# MidiMon_B.net
KiCad netlist of a schematic drawn in EAGLE
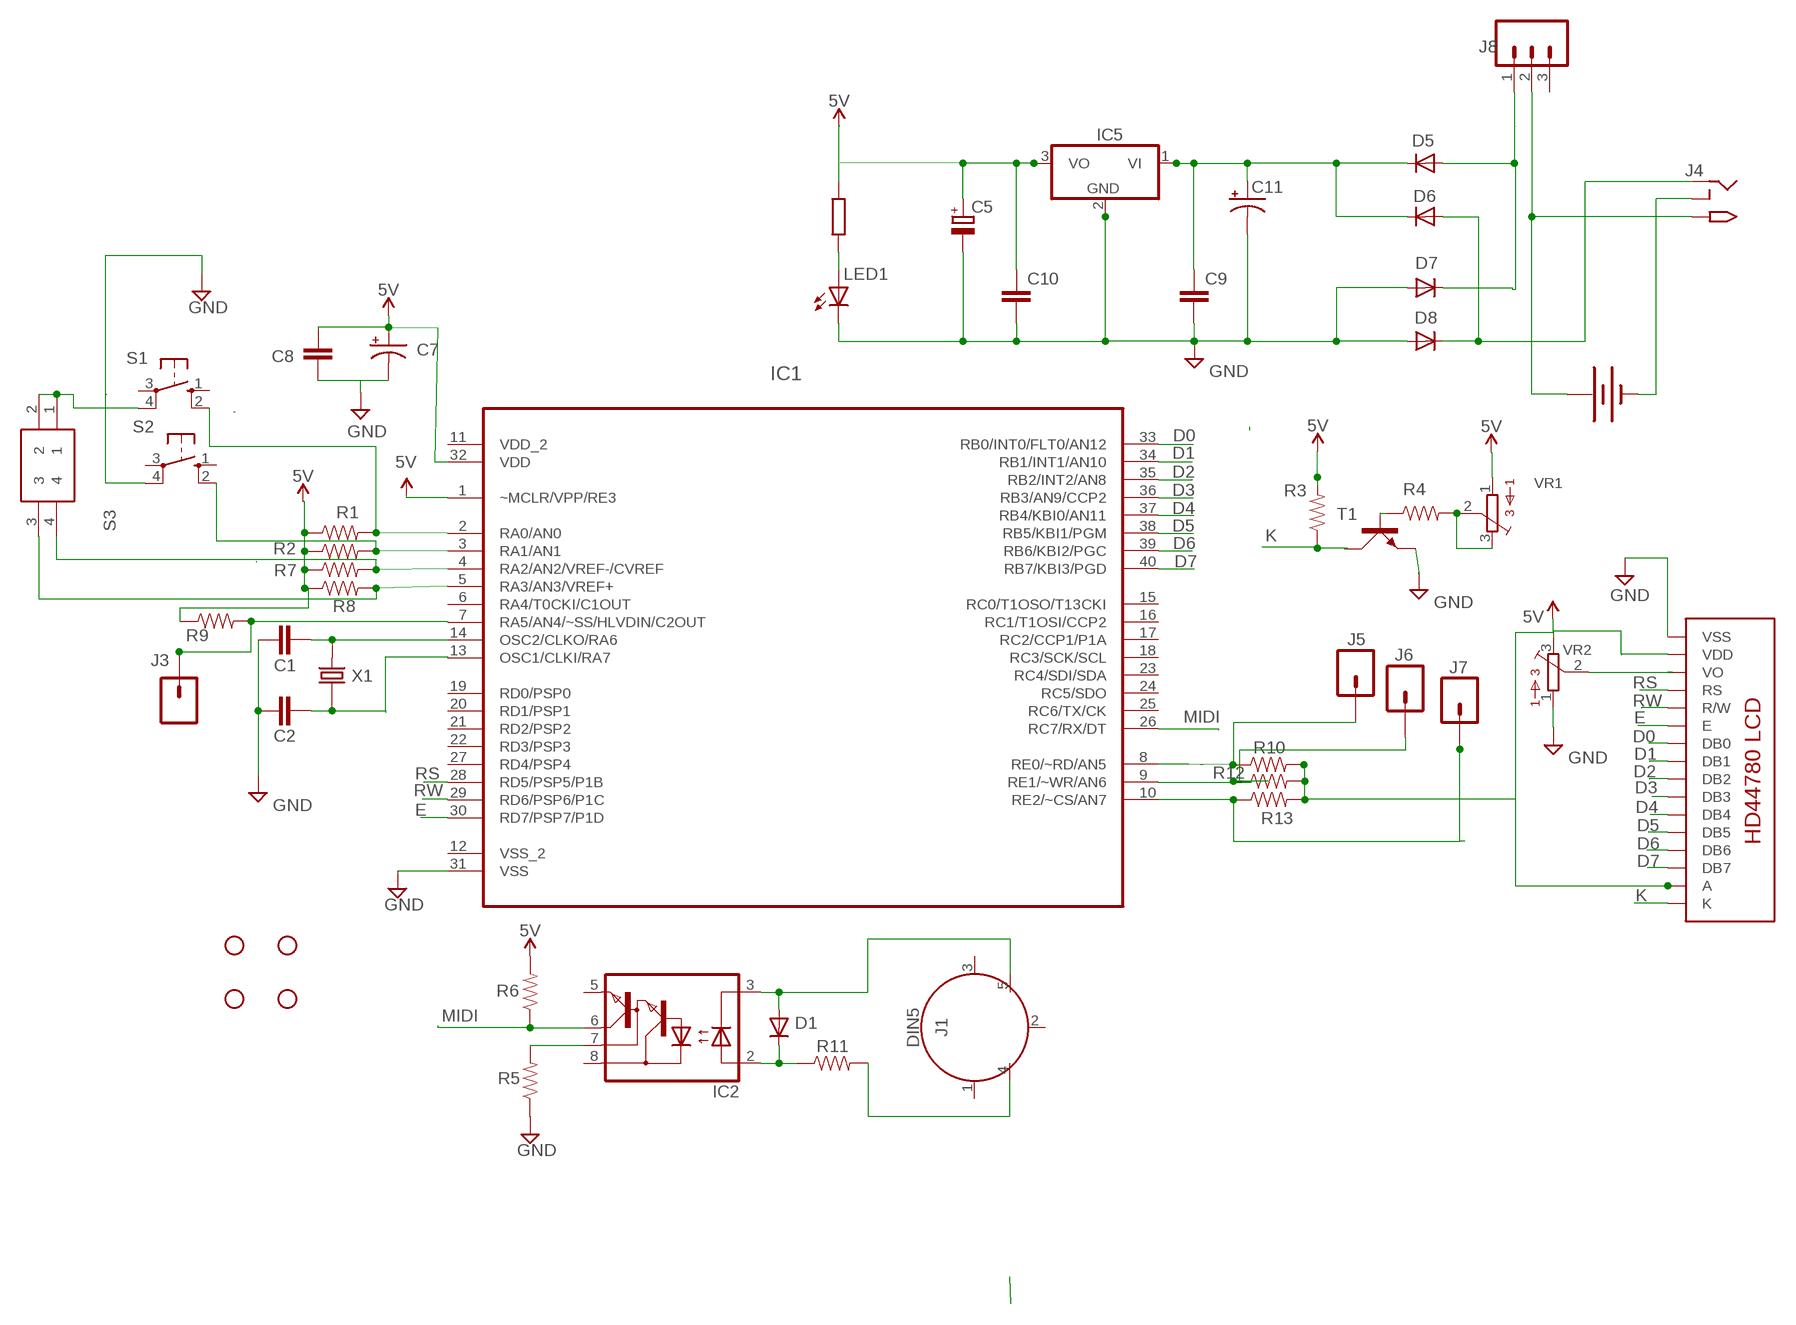
[diagram p0: schematic, sheet 1]

(export (version "E")
  (design (tool "Eeschema 10.0.6"))
  (components
    (comp (ref "BAT1")
      (value "BATTERY")
      (footprint "eagle-import:PP3_BATTERBOX")
      (libsource (lib "eagle-import") (part "BATTERY"))
    )
    (comp (ref "C1")
      (value "18pF")
      (footprint "eagle-import:CAP-PTH-2.54")
      (libsource (lib "eagle-import") (part "22PF-PTH-2.54MM-200V-5%"))
    )
    (comp (ref "C2")
      (value "18pF")
      (footprint "eagle-import:CAP-PTH-2.54")
      (libsource (lib "eagle-import") (part "22PF-PTH-2.54MM-200V-5%"))
    )
    (comp (ref "C5")
      (value "10uf")
      (footprint "eagle-import:E2,5-7")
      (libsource (lib "eagle-import") (part "CPOL-EUE2.5-7"))
    )
    (comp (ref "C7")
      (value "10uF")
      (footprint "eagle-import:CPOL-RADIAL-2.5MM-5MM")
      (libsource (lib "eagle-import") (part "10UF-POLAR-RADIAL-2.5MM-25V-20%"))
    )
    (comp (ref "C8")
      (value "0.1uF")
      (footprint "eagle-import:CAP-PTH-SMALL-KIT")
      (libsource (lib "eagle-import") (part "0.1UF-KIT-EZ-50V-20%"))
    )
    (comp (ref "C9")
      (value "330nf")
      (footprint "eagle-import:C025-024X044")
      (libsource (lib "eagle-import") (part "C-EU025-024X044"))
    )
    (comp (ref "C10")
      (value "100nf")
      (footprint "eagle-import:C025-024X044")
      (libsource (lib "eagle-import") (part "C-EU025-024X044"))
    )
    (comp (ref "C11")
      (value "2200uf")
      (footprint "eagle-import:E5-10,5")
      (libsource (lib "eagle-import") (part "CPOL-USE5-10.5"))
    )
    (comp (ref "D1")
      (value "DIODEDO-1N4148")
      (footprint "eagle-import:DO-1N4148")
      (libsource (lib "eagle-import") (part "DIODEDO-1N4148"))
    )
    (comp (ref "D5")
      (value "1N4004")
      (footprint "eagle-import:DO-VERT")
      (libsource (lib "eagle-import") (part "1N4004"))
    )
    (comp (ref "D6")
      (value "1N4004")
      (footprint "eagle-import:DO-VERT")
      (libsource (lib "eagle-import") (part "1N4004"))
    )
    (comp (ref "D7")
      (value "1N4004")
      (footprint "eagle-import:DO-VERT")
      (libsource (lib "eagle-import") (part "1N4004"))
    )
    (comp (ref "D8")
      (value "1N4004")
      (footprint "eagle-import:DO-VERT")
      (libsource (lib "eagle-import") (part "1N4004"))
    )
    (comp (ref "H1")
      (value "STAND-OFFTIGHT")
      (footprint "eagle-import:STAND-OFF-TIGHT")
      (libsource (lib "eagle-import") (part "STAND-OFFTIGHT"))
    )
    (comp (ref "H2")
      (value "STAND-OFFTIGHT")
      (footprint "eagle-import:STAND-OFF-TIGHT")
      (libsource (lib "eagle-import") (part "STAND-OFFTIGHT"))
    )
    (comp (ref "H3")
      (value "STAND-OFFTIGHT")
      (footprint "eagle-import:STAND-OFF-TIGHT")
      (libsource (lib "eagle-import") (part "STAND-OFFTIGHT"))
    )
    (comp (ref "H4")
      (value "STAND-OFFTIGHT")
      (footprint "eagle-import:STAND-OFF-TIGHT")
      (libsource (lib "eagle-import") (part "STAND-OFFTIGHT"))
    )
    (comp (ref "IC1")
      (value "PIC18F4520-I/P")
      (footprint "eagle-import:DIP254P1524X533-40")
      (fields (field (name "MF") "Microchip"))
      (libsource (lib "eagle-import") (part "PIC18F4520-I/P"))
    )
    (comp (ref "IC2")
      (value "6N138")
      (footprint "eagle-import:DIL08")
      (fields (field (name "MF") "VISHAY/TELEFUNKEN"))
      (libsource (lib "eagle-import") (part "6N138"))
    )
    (comp (ref "IC5")
      (value "7805TV")
      (footprint "eagle-import:TO220V")
      (libsource (lib "eagle-import") (part "78TV05"))
    )
    (comp (ref "J1")
      (value "DIN5")
      (footprint "eagle-import:DIN5-RA-PTH")
      (libsource (lib "eagle-import") (part "DIN5"))
    )
    (comp (ref "J3")
      (value "CONN_01")
      (footprint "eagle-import:1X01")
      (libsource (lib "eagle-import") (part "CONN_01"))
    )
    (comp (ref "J4")
      (value "2.1MMJACKTHM")
      (footprint "eagle-import:PJ-102A")
      (libsource (lib "eagle-import") (part "2.1MMJACKTHM"))
    )
    (comp (ref "J5")
      (value "CONN_01")
      (footprint "eagle-import:1X01")
      (libsource (lib "eagle-import") (part "CONN_01"))
    )
    (comp (ref "J6")
      (value "CONN_01")
      (footprint "eagle-import:1X01")
      (libsource (lib "eagle-import") (part "CONN_01"))
    )
    (comp (ref "J7")
      (value "CONN_01")
      (footprint "eagle-import:1X01")
      (libsource (lib "eagle-import") (part "CONN_01"))
    )
    (comp (ref "J8")
      (value "CONN_03")
      (footprint "eagle-import:1X03")
      (libsource (lib "eagle-import") (part "CONN_03"))
    )
    (comp (ref "LED1")
      (value "LED3MM")
      (footprint "eagle-import:LED3MM")
      (libsource (lib "eagle-import") (part "LED3MM"))
    )
    (comp (ref "R1")
      (value "10k")
      (footprint "eagle-import:AXIAL-0.3")
      (libsource (lib "eagle-import") (part "1KOHM-HORIZ-1/4W-5%"))
    )
    (comp (ref "R2")
      (value "10k")
      (footprint "eagle-import:AXIAL-0.3")
      (libsource (lib "eagle-import") (part "1KOHM-HORIZ-1/4W-5%"))
    )
    (comp (ref "R3")
      (value "10k")
      (footprint "eagle-import:AXIAL-0.3")
      (libsource (lib "eagle-import") (part "1KOHM-HORIZ-1/4W-5%"))
    )
    (comp (ref "R4")
      (value "10k")
      (footprint "eagle-import:AXIAL-0.3")
      (libsource (lib "eagle-import") (part "1KOHM-HORIZ-1/4W-5%"))
    )
    (comp (ref "R5")
      (value "5.6k")
      (footprint "eagle-import:AXIAL-0.3")
      (libsource (lib "eagle-import") (part "1KOHM-HORIZ-1/4W-5%"))
    )
    (comp (ref "R6")
      (value "1.2k")
      (footprint "eagle-import:AXIAL-0.3")
      (libsource (lib "eagle-import") (part "1KOHM-HORIZ-1/4W-5%"))
    )
    (comp (ref "R7")
      (value "10k")
      (footprint "eagle-import:AXIAL-0.3")
      (libsource (lib "eagle-import") (part "1KOHM-HORIZ-1/4W-5%"))
    )
    (comp (ref "R8")
      (value "10k")
      (footprint "eagle-import:AXIAL-0.3")
      (libsource (lib "eagle-import") (part "1KOHM-HORIZ-1/4W-5%"))
    )
    (comp (ref "R9")
      (value "10k")
      (footprint "eagle-import:AXIAL-0.3")
      (libsource (lib "eagle-import") (part "1KOHM-HORIZ-1/4W-5%"))
    )
    (comp (ref "R10")
      (value "10k")
      (footprint "eagle-import:AXIAL-0.3")
      (libsource (lib "eagle-import") (part "1KOHM-HORIZ-1/4W-5%"))
    )
    (comp (ref "R11")
      (value "220")
      (footprint "eagle-import:AXIAL-0.3")
      (libsource (lib "eagle-import") (part "1KOHM-HORIZ-1/4W-5%"))
    )
    (comp (ref "R12")
      (value "10k")
      (footprint "eagle-import:AXIAL-0.3")
      (libsource (lib "eagle-import") (part "1KOHM-HORIZ-1/4W-5%"))
    )
    (comp (ref "R13")
      (value "10k")
      (footprint "eagle-import:AXIAL-0.3")
      (libsource (lib "eagle-import") (part "1KOHM-HORIZ-1/4W-5%"))
    )
    (comp (ref "R20")
      (value "1k")
      (footprint "eagle-import:0207_7")
      (libsource (lib "eagle-import") (part "R-EU_0207/7"))
    )
    (comp (ref "S1")
      (value "40-XX")
      (footprint "eagle-import:B3F-40XX")
      (fields (field (name "MF") "OMRON COMPONENTS USA") (field (name "MPN") "B3F-4000"))
      (libsource (lib "eagle-import") (part "40-XX"))
    )
    (comp (ref "S2")
      (value "40-XX")
      (footprint "eagle-import:B3F-40XX")
      (fields (field (name "MF") "OMRON COMPONENTS USA") (field (name "MPN") "B3F-4000"))
      (libsource (lib "eagle-import") (part "40-XX"))
    )
    (comp (ref "S3")
      (value "195-2MST")
      (footprint "eagle-import:DIPS774W56P254L726H790Q4N")
      (fields (field (name "MOUSER_PART_NUMBER") "774-1952MST"))
      (libsource (lib "eagle-import") (part "195-2MST"))
    )
    (comp (ref "T1")
      (value "2N3904")
      (footprint "eagle-import:TO92D")
      (libsource (lib "eagle-import") (part "2N3904"))
    )
    (comp (ref "U$2")
      (value "LCD-HD4478020X4-3HOLES")
      (footprint "eagle-import:LCD-20X4-3HOLES")
      (libsource (lib "eagle-import") (part "LCD-HD4478020X4-3HOLES"))
    )
    (comp (ref "VR1")
      (value "BOURNS_3362P_TRIMMERP")
      (footprint "eagle-import:BOURNS_3362P_TRIMMER")
      (libsource (lib "eagle-import") (part "BOURNS_3362P_TRIMMERP"))
    )
    (comp (ref "VR2")
      (value "BOURNS_3362P_TRIMMERP")
      (footprint "eagle-import:BOURNS_3362P_TRIMMER")
      (libsource (lib "eagle-import") (part "BOURNS_3362P_TRIMMERP"))
    )
    (comp (ref "X1")
      (value "ECS-100-18-4X")
      (footprint "eagle-import:XTAL_ECS-100-18-4X")
      (fields (field (name "DIGI-KEY_PART_NUMBER") "X1080-ND") (field (name "MF") "ECS Inc."))
      (libsource (lib "eagle-import") (part "ECS-100-18-4X"))
    )
  )
  (nets
    (net (code "1") (name "/D0") (class "Default")
      (node (ref "IC1") (pin "33") (pinfunction "RB0/INT0/FLT0/AN12_33") (pintype "bidirectional"))
      (node (ref "U$2") (pin "P$7") (pinfunction "DB0_P$7") (pintype "bidirectional"))
    )
    (net (code "2") (name "/D1") (class "Default")
      (node (ref "IC1") (pin "34") (pinfunction "RB1/INT1/AN10_34") (pintype "bidirectional"))
      (node (ref "U$2") (pin "P$8") (pinfunction "DB1_P$8") (pintype "bidirectional"))
    )
    (net (code "3") (name "/D2") (class "Default")
      (node (ref "IC1") (pin "35") (pinfunction "RB2/INT2/AN8_35") (pintype "bidirectional"))
      (node (ref "U$2") (pin "P$9") (pinfunction "DB2_P$9") (pintype "bidirectional"))
    )
    (net (code "4") (name "/D3") (class "Default")
      (node (ref "IC1") (pin "36") (pinfunction "RB3/AN9/CCP2_36") (pintype "bidirectional"))
      (node (ref "U$2") (pin "P$10") (pinfunction "DB3_P$10") (pintype "bidirectional"))
    )
    (net (code "5") (name "/D4") (class "Default")
      (node (ref "IC1") (pin "37") (pinfunction "RB4/KBI0/AN11_37") (pintype "bidirectional"))
      (node (ref "U$2") (pin "P$11") (pinfunction "DB4_P$11") (pintype "bidirectional"))
    )
    (net (code "6") (name "/D5") (class "Default")
      (node (ref "IC1") (pin "38") (pinfunction "RB5/KBI1/PGM_38") (pintype "bidirectional"))
      (node (ref "U$2") (pin "P$12") (pinfunction "DB5_P$12") (pintype "bidirectional"))
    )
    (net (code "7") (name "/D6") (class "Default")
      (node (ref "IC1") (pin "39") (pinfunction "RB6/KBI2/PGC_39") (pintype "bidirectional"))
      (node (ref "U$2") (pin "P$13") (pinfunction "DB6_P$13") (pintype "bidirectional"))
    )
    (net (code "8") (name "/D7") (class "Default")
      (node (ref "IC1") (pin "40") (pinfunction "RB7/KBI3/PGD_40") (pintype "bidirectional"))
      (node (ref "U$2") (pin "P$14") (pinfunction "DB7_P$14") (pintype "bidirectional"))
    )
    (net (code "9") (name "/E") (class "Default")
      (node (ref "IC1") (pin "30") (pinfunction "RD7/PSP7/P1D_30") (pintype "bidirectional"))
      (node (ref "U$2") (pin "P$6") (pinfunction "E_P$6") (pintype "input"))
    )
    (net (code "10") (name "/K") (class "Default")
      (node (ref "R3") (pin "P$1") (pinfunction "1_P$1") (pintype "passive"))
      (node (ref "T1") (pin "C") (pinfunction "C_C") (pintype "passive"))
      (node (ref "U$2") (pin "P$16") (pinfunction "K_P$16") (pintype "power_in"))
    )
    (net (code "11") (name "/MIDI") (class "Default")
      (node (ref "IC1") (pin "26") (pinfunction "RC7/RX/DT_26") (pintype "bidirectional"))
      (node (ref "IC2") (pin "6") (pinfunction "VO_6") (pintype "passive"))
      (node (ref "R6") (pin "P$1") (pinfunction "1_P$1") (pintype "passive"))
    )
    (net (code "12") (name "/RS") (class "Default")
      (node (ref "IC1") (pin "28") (pinfunction "RD5/PSP5/P1B_28") (pintype "bidirectional"))
      (node (ref "U$2") (pin "P$4") (pinfunction "RS_P$4") (pintype "input"))
    )
    (net (code "13") (name "/RW") (class "Default")
      (node (ref "IC1") (pin "29") (pinfunction "RD6/PSP6/P1C_29") (pintype "bidirectional"))
      (node (ref "U$2") (pin "P$5") (pinfunction "R/W_P$5") (pintype "input"))
    )
    (net (code "14") (name "/VDD_2") (class "Default")
      (node (ref "IC1") (pin "11") (pinfunction "VDD_2_11") (pintype "power_in"))
    )
    (net (code "15") (name "/VSS_2") (class "Default")
      (node (ref "IC1") (pin "12") (pinfunction "VSS_2_12") (pintype "power_in"))
    )
    (net (code "16") (name "5V") (class "Default")
      (node (ref "C7") (pin "1") (pinfunction "+_1") (pintype "passive"))
      (node (ref "C8") (pin "2") (pinfunction "2_2") (pintype "passive"))
      (node (ref "IC1") (pin "1") (pinfunction "~{MCLR/VPP/RE3}_1") (pintype "input"))
      (node (ref "IC1") (pin "32") (pinfunction "VDD_32") (pintype "power_in"))
      (node (ref "R1") (pin "P$1") (pinfunction "1_P$1") (pintype "passive"))
      (node (ref "R10") (pin "P$2") (pinfunction "2_P$2") (pintype "passive"))
      (node (ref "R12") (pin "P$2") (pinfunction "2_P$2") (pintype "passive"))
      (node (ref "R13") (pin "P$2") (pinfunction "2_P$2") (pintype "passive"))
      (node (ref "R2") (pin "P$1") (pinfunction "1_P$1") (pintype "passive"))
      (node (ref "R3") (pin "P$2") (pinfunction "2_P$2") (pintype "passive"))
      (node (ref "R6") (pin "P$2") (pinfunction "2_P$2") (pintype "passive"))
      (node (ref "R7") (pin "P$1") (pinfunction "1_P$1") (pintype "passive"))
      (node (ref "R8") (pin "P$1") (pinfunction "1_P$1") (pintype "passive"))
      (node (ref "R9") (pin "P$1") (pinfunction "1_P$1") (pintype "passive"))
      (node (ref "U$2") (pin "P$15") (pinfunction "A_P$15") (pintype "power_in"))
      (node (ref "VR1") (pin "1") (pinfunction "1_1") (pintype "passive"))
    )
    (net (code "17") (name "GND") (class "Default")
      (node (ref "C1") (pin "1") (pinfunction "1_1") (pintype "passive"))
      (node (ref "C10") (pin "2") (pinfunction "2_2") (pintype "passive"))
      (node (ref "C11") (pin "-") (pinfunction "-_-") (pintype "passive"))
      (node (ref "C2") (pin "1") (pinfunction "1_1") (pintype "passive"))
      (node (ref "C5") (pin "-") (pinfunction "-_-") (pintype "passive"))
      (node (ref "C7") (pin "2") (pinfunction "-_2") (pintype "passive"))
      (node (ref "C8") (pin "1") (pinfunction "1_1") (pintype "passive"))
      (node (ref "C9") (pin "2") (pinfunction "2_2") (pintype "passive"))
      (node (ref "D7") (pin "A") (pinfunction "A_A") (pintype "passive"))
      (node (ref "D8") (pin "A") (pinfunction "A_A") (pintype "passive"))
      (node (ref "IC1") (pin "31") (pinfunction "VSS_31") (pintype "power_in"))
      (node (ref "IC5") (pin "2") (pinfunction "GND_2") (pintype "passive"))
      (node (ref "LED1") (pin "K") (pinfunction "C_K") (pintype "passive"))
      (node (ref "R5") (pin "P$1") (pinfunction "1_P$1") (pintype "passive"))
      (node (ref "S1") (pin "4") (pinfunction "P1_4") (pintype "passive"))
      (node (ref "S2") (pin "4") (pinfunction "P1_4") (pintype "passive"))
      (node (ref "S3") (pin "1") (pinfunction "1_1") (pintype "bidirectional"))
      (node (ref "S3") (pin "2") (pinfunction "2_2") (pintype "bidirectional"))
      (node (ref "T1") (pin "E") (pinfunction "E_E") (pintype "passive"))
      (node (ref "U$2") (pin "P$1") (pinfunction "VSS_P$1") (pintype "power_in"))
      (node (ref "VR2") (pin "1") (pinfunction "1_1") (pintype "passive"))
    )
    (net (code "18") (name "Net-(BAT1-+)") (class "Default")
      (node (ref "BAT1") (pin "9V") (pinfunction "+_9V") (pintype "power_in"))
      (node (ref "J4") (pin "TIP") (pinfunction "TIP_TIP") (pintype "bidirectional"))
      (node (ref "J8") (pin "2") (pinfunction "2_2") (pintype "passive"))
    )
    (net (code "19") (name "Net-(BAT1--)") (class "Default")
      (node (ref "BAT1") (pin "0V") (pinfunction "-_0V") (pintype "power_in"))
      (node (ref "J4") (pin "RING_SW") (pinfunction "RING_SW_RING_SW") (pintype "bidirectional"))
    )
    (net (code "20") (name "Net-(D5-PadA)") (class "Default")
      (node (ref "D5") (pin "A") (pinfunction "A_A") (pintype "passive"))
      (node (ref "D7") (pin "C") (pinfunction "C_C") (pintype "passive"))
      (node (ref "J8") (pin "1") (pinfunction "1_1") (pintype "passive"))
    )
    (net (code "21") (name "Net-(D6-PadA)") (class "Default")
      (node (ref "D6") (pin "A") (pinfunction "A_A") (pintype "passive"))
      (node (ref "D8") (pin "C") (pinfunction "C_C") (pintype "passive"))
      (node (ref "J4") (pin "RING") (pinfunction "RING_RING") (pintype "bidirectional"))
    )
    (net (code "22") (name "Net-(IC1-OSC1{slash}CLKI{slash}RA7)") (class "Default")
      (node (ref "C2") (pin "2") (pinfunction "2_2") (pintype "passive"))
      (node (ref "IC1") (pin "13") (pinfunction "OSC1/CLKI/RA7_13") (pintype "bidirectional"))
      (node (ref "X1") (pin "1") (pinfunction "1_1") (pintype "passive"))
    )
    (net (code "23") (name "Net-(IC1-OSC2{slash}CLKO{slash}RA6)") (class "Default")
      (node (ref "C1") (pin "2") (pinfunction "2_2") (pintype "passive"))
      (node (ref "IC1") (pin "14") (pinfunction "OSC2/CLKO/RA6_14") (pintype "bidirectional"))
      (node (ref "X1") (pin "2") (pinfunction "2_2") (pintype "passive"))
    )
    (net (code "24") (name "Net-(IC1-RA0{slash}AN0)") (class "Default")
      (node (ref "IC1") (pin "2") (pinfunction "RA0/AN0_2") (pintype "bidirectional"))
      (node (ref "R1") (pin "P$2") (pinfunction "2_P$2") (pintype "passive"))
      (node (ref "S1") (pin "2") (pinfunction "S1_2") (pintype "passive"))
    )
    (net (code "25") (name "Net-(IC1-RA1{slash}AN1)") (class "Default")
      (node (ref "IC1") (pin "3") (pinfunction "RA1/AN1_3") (pintype "bidirectional"))
      (node (ref "R2") (pin "P$2") (pinfunction "2_P$2") (pintype "passive"))
      (node (ref "S2") (pin "2") (pinfunction "S1_2") (pintype "passive"))
    )
    (net (code "26") (name "Net-(IC1-RA2{slash}AN2{slash}VREF-{slash}CVREF)") (class "Default")
      (node (ref "IC1") (pin "4") (pinfunction "RA2/AN2/VREF-/CVREF_4") (pintype "bidirectional"))
      (node (ref "R7") (pin "P$2") (pinfunction "2_P$2") (pintype "passive"))
      (node (ref "S3") (pin "4") (pinfunction "4_4") (pintype "bidirectional"))
    )
    (net (code "27") (name "Net-(IC1-RA3{slash}AN3{slash}VREF+)") (class "Default")
      (node (ref "IC1") (pin "5") (pinfunction "RA3/AN3/VREF+_5") (pintype "bidirectional"))
      (node (ref "R8") (pin "P$2") (pinfunction "2_P$2") (pintype "passive"))
      (node (ref "S3") (pin "3") (pinfunction "3_3") (pintype "bidirectional"))
    )
    (net (code "28") (name "Net-(IC1-RA5{slash}AN4{slash}~{SS{slash}HLVDIN{slash}C2OUT})") (class "Default")
      (node (ref "IC1") (pin "7") (pinfunction "RA5/AN4/~{SS/HLVDIN/C2OUT}_7") (pintype "bidirectional"))
      (node (ref "J3") (pin "1") (pinfunction "1_1") (pintype "passive"))
      (node (ref "R9") (pin "P$2") (pinfunction "2_P$2") (pintype "passive"))
    )
    (net (code "29") (name "Net-(IC1-RE0{slash}~{RD{slash}AN5})") (class "Default")
      (node (ref "IC1") (pin "8") (pinfunction "RE0/~{RD/AN5}_8") (pintype "bidirectional"))
      (node (ref "J5") (pin "1") (pinfunction "1_1") (pintype "passive"))
      (node (ref "R10") (pin "P$1") (pinfunction "1_P$1") (pintype "passive"))
    )
    (net (code "30") (name "Net-(IC1-RE1{slash}~{WR{slash}AN6})") (class "Default")
      (node (ref "IC1") (pin "9") (pinfunction "RE1/~{WR/AN6}_9") (pintype "bidirectional"))
      (node (ref "J6") (pin "1") (pinfunction "1_1") (pintype "passive"))
      (node (ref "R12") (pin "P$1") (pinfunction "1_P$1") (pintype "passive"))
    )
    (net (code "31") (name "Net-(IC1-RE2{slash}~{CS{slash}AN7})") (class "Default")
      (node (ref "IC1") (pin "10") (pinfunction "RE2/~{CS/AN7}_10") (pintype "bidirectional"))
      (node (ref "J7") (pin "1") (pinfunction "1_1") (pintype "passive"))
      (node (ref "R13") (pin "P$1") (pinfunction "1_P$1") (pintype "passive"))
    )
    (net (code "32") (name "Net-(IC2-A)") (class "Default")
      (node (ref "D1") (pin "C") (pinfunction "C_C") (pintype "passive"))
      (node (ref "IC2") (pin "2") (pinfunction "A_2") (pintype "passive"))
      (node (ref "R11") (pin "P$1") (pinfunction "1_P$1") (pintype "passive"))
    )
    (net (code "33") (name "Net-(IC2-C)") (class "Default")
      (node (ref "D1") (pin "A") (pinfunction "A_A") (pintype "passive"))
      (node (ref "IC2") (pin "3") (pinfunction "C_3") (pintype "passive"))
      (node (ref "J1") (pin "5") (pinfunction "5_5") (pintype "bidirectional"))
    )
    (net (code "34") (name "Net-(IC2-VB)") (class "Default")
      (node (ref "IC2") (pin "7") (pinfunction "VB_7") (pintype "passive"))
      (node (ref "R5") (pin "P$2") (pinfunction "2_P$2") (pintype "passive"))
    )
    (net (code "35") (name "Net-(IC5-VI)") (class "Default")
      (node (ref "C11") (pin "+") (pinfunction "+_+") (pintype "passive"))
      (node (ref "C9") (pin "1") (pinfunction "1_1") (pintype "passive"))
      (node (ref "D5") (pin "C") (pinfunction "C_C") (pintype "passive"))
      (node (ref "D6") (pin "C") (pinfunction "C_C") (pintype "passive"))
      (node (ref "IC5") (pin "1") (pinfunction "VI_1") (pintype "input"))
    )
    (net (code "36") (name "Net-(IC5-VO)") (class "Default")
      (node (ref "C10") (pin "1") (pinfunction "1_1") (pintype "passive"))
      (node (ref "C5") (pin "+") (pinfunction "+_+") (pintype "passive"))
      (node (ref "IC5") (pin "3") (pinfunction "VO_3") (pintype "passive"))
      (node (ref "R20") (pin "1") (pinfunction "1_1") (pintype "passive"))
    )
    (net (code "37") (name "Net-(LED1-PadA)") (class "Default")
      (node (ref "LED1") (pin "A") (pinfunction "A_A") (pintype "passive"))
      (node (ref "R20") (pin "2") (pinfunction "2_2") (pintype "passive"))
    )
    (net (code "38") (name "Net-(R4-1)") (class "Default")
      (node (ref "R4") (pin "P$1") (pinfunction "1_P$1") (pintype "passive"))
      (node (ref "T1") (pin "B") (pinfunction "B_B") (pintype "passive"))
    )
    (net (code "39") (name "Net-(R4-2)") (class "Default")
      (node (ref "R4") (pin "P$2") (pinfunction "2_P$2") (pintype "passive"))
      (node (ref "VR1") (pin "2") (pinfunction "2_2") (pintype "passive"))
      (node (ref "VR1") (pin "3") (pinfunction "3_3") (pintype "passive"))
    )
    (net (code "40") (name "Net-(R11-2)") (class "Default")
      (node (ref "J1") (pin "4") (pinfunction "4_4") (pintype "bidirectional"))
      (node (ref "R11") (pin "P$2") (pinfunction "2_P$2") (pintype "passive"))
    )
    (net (code "41") (name "Net-(U$2-VDD)") (class "Default")
      (node (ref "U$2") (pin "P$2") (pinfunction "VDD_P$2") (pintype "power_in"))
      (node (ref "VR2") (pin "3") (pinfunction "3_3") (pintype "passive"))
    )
    (net (code "42") (name "Net-(U$2-VO)") (class "Default")
      (node (ref "U$2") (pin "P$3") (pinfunction "VO_P$3") (pintype "bidirectional"))
      (node (ref "VR2") (pin "2") (pinfunction "2_2") (pintype "passive"))
    )
    (net (code "43") (name "unconnected-(IC1-RA4{slash}T0CKI{slash}C1OUT-Pad6)") (class "Default")
      (node (ref "IC1") (pin "6") (pinfunction "RA4/T0CKI/C1OUT_6") (pintype "bidirectional"))
    )
    (net (code "44") (name "unconnected-(IC1-RC0{slash}T1OSO{slash}T13CKI-Pad15)") (class "Default")
      (node (ref "IC1") (pin "15") (pinfunction "RC0/T1OSO/T13CKI_15") (pintype "bidirectional"))
    )
    (net (code "45") (name "unconnected-(IC1-RC1{slash}T1OSI{slash}CCP2-Pad16)") (class "Default")
      (node (ref "IC1") (pin "16") (pinfunction "RC1/T1OSI/CCP2_16") (pintype "bidirectional"))
    )
    (net (code "46") (name "unconnected-(IC1-RC2{slash}CCP1{slash}P1A-Pad17)") (class "Default")
      (node (ref "IC1") (pin "17") (pinfunction "RC2/CCP1/P1A_17") (pintype "bidirectional"))
    )
    (net (code "47") (name "unconnected-(IC1-RC3{slash}SCK{slash}SCL-Pad18)") (class "Default")
      (node (ref "IC1") (pin "18") (pinfunction "RC3/SCK/SCL_18") (pintype "bidirectional"))
    )
    (net (code "48") (name "unconnected-(IC1-RC4{slash}SDI{slash}SDA-Pad23)") (class "Default")
      (node (ref "IC1") (pin "23") (pinfunction "RC4/SDI/SDA_23") (pintype "bidirectional"))
    )
    (net (code "49") (name "unconnected-(IC1-RC5{slash}SDO-Pad24)") (class "Default")
      (node (ref "IC1") (pin "24") (pinfunction "RC5/SDO_24") (pintype "bidirectional"))
    )
    (net (code "50") (name "unconnected-(IC1-RC6{slash}TX{slash}CK-Pad25)") (class "Default")
      (node (ref "IC1") (pin "25") (pinfunction "RC6/TX/CK_25") (pintype "bidirectional"))
    )
    (net (code "51") (name "unconnected-(IC1-RD0{slash}PSP0-Pad19)") (class "Default")
      (node (ref "IC1") (pin "19") (pinfunction "RD0/PSP0_19") (pintype "bidirectional"))
    )
    (net (code "52") (name "unconnected-(IC1-RD1{slash}PSP1-Pad20)") (class "Default")
      (node (ref "IC1") (pin "20") (pinfunction "RD1/PSP1_20") (pintype "bidirectional"))
    )
    (net (code "53") (name "unconnected-(IC1-RD2{slash}PSP2-Pad21)") (class "Default")
      (node (ref "IC1") (pin "21") (pinfunction "RD2/PSP2_21") (pintype "bidirectional"))
    )
    (net (code "54") (name "unconnected-(IC1-RD3{slash}PSP3-Pad22)") (class "Default")
      (node (ref "IC1") (pin "22") (pinfunction "RD3/PSP3_22") (pintype "bidirectional"))
    )
    (net (code "55") (name "unconnected-(IC1-RD4{slash}PSP4-Pad27)") (class "Default")
      (node (ref "IC1") (pin "27") (pinfunction "RD4/PSP4_27") (pintype "bidirectional"))
    )
    (net (code "56") (name "unconnected-(IC2-GND-Pad5)") (class "Default")
      (node (ref "IC2") (pin "5") (pinfunction "GND_5") (pintype "passive"))
    )
    (net (code "57") (name "unconnected-(IC2-VCC-Pad8)") (class "Default")
      (node (ref "IC2") (pin "8") (pinfunction "VCC_8") (pintype "passive"))
    )
    (net (code "58") (name "unconnected-(J1-Pad1)") (class "Default")
      (node (ref "J1") (pin "1") (pinfunction "1_1") (pintype "bidirectional"))
    )
    (net (code "59") (name "unconnected-(J1-Pad2)") (class "Default")
      (node (ref "J1") (pin "2") (pinfunction "2_2") (pintype "bidirectional"))
    )
    (net (code "60") (name "unconnected-(J1-Pad3)") (class "Default")
      (node (ref "J1") (pin "3") (pinfunction "3_3") (pintype "bidirectional"))
    )
    (net (code "61") (name "unconnected-(J8-Pad3)") (class "Default")
      (node (ref "J8") (pin "3") (pinfunction "3_3") (pintype "passive"))
    )
    (net (code "62") (name "unconnected-(S1-P-Pad3)") (class "Default")
      (node (ref "S1") (pin "3") (pinfunction "P_3") (pintype "passive"))
    )
    (net (code "63") (name "unconnected-(S1-S-Pad1)") (class "Default")
      (node (ref "S1") (pin "1") (pinfunction "S_1") (pintype "passive"))
    )
    (net (code "64") (name "unconnected-(S2-P-Pad3)") (class "Default")
      (node (ref "S2") (pin "3") (pinfunction "P_3") (pintype "passive"))
    )
    (net (code "65") (name "unconnected-(S2-S-Pad1)") (class "Default")
      (node (ref "S2") (pin "1") (pinfunction "S_1") (pintype "passive"))
    )
  )
)
